# Safety_Valve.net
KiCad netlist of a schematic drawn in EAGLE
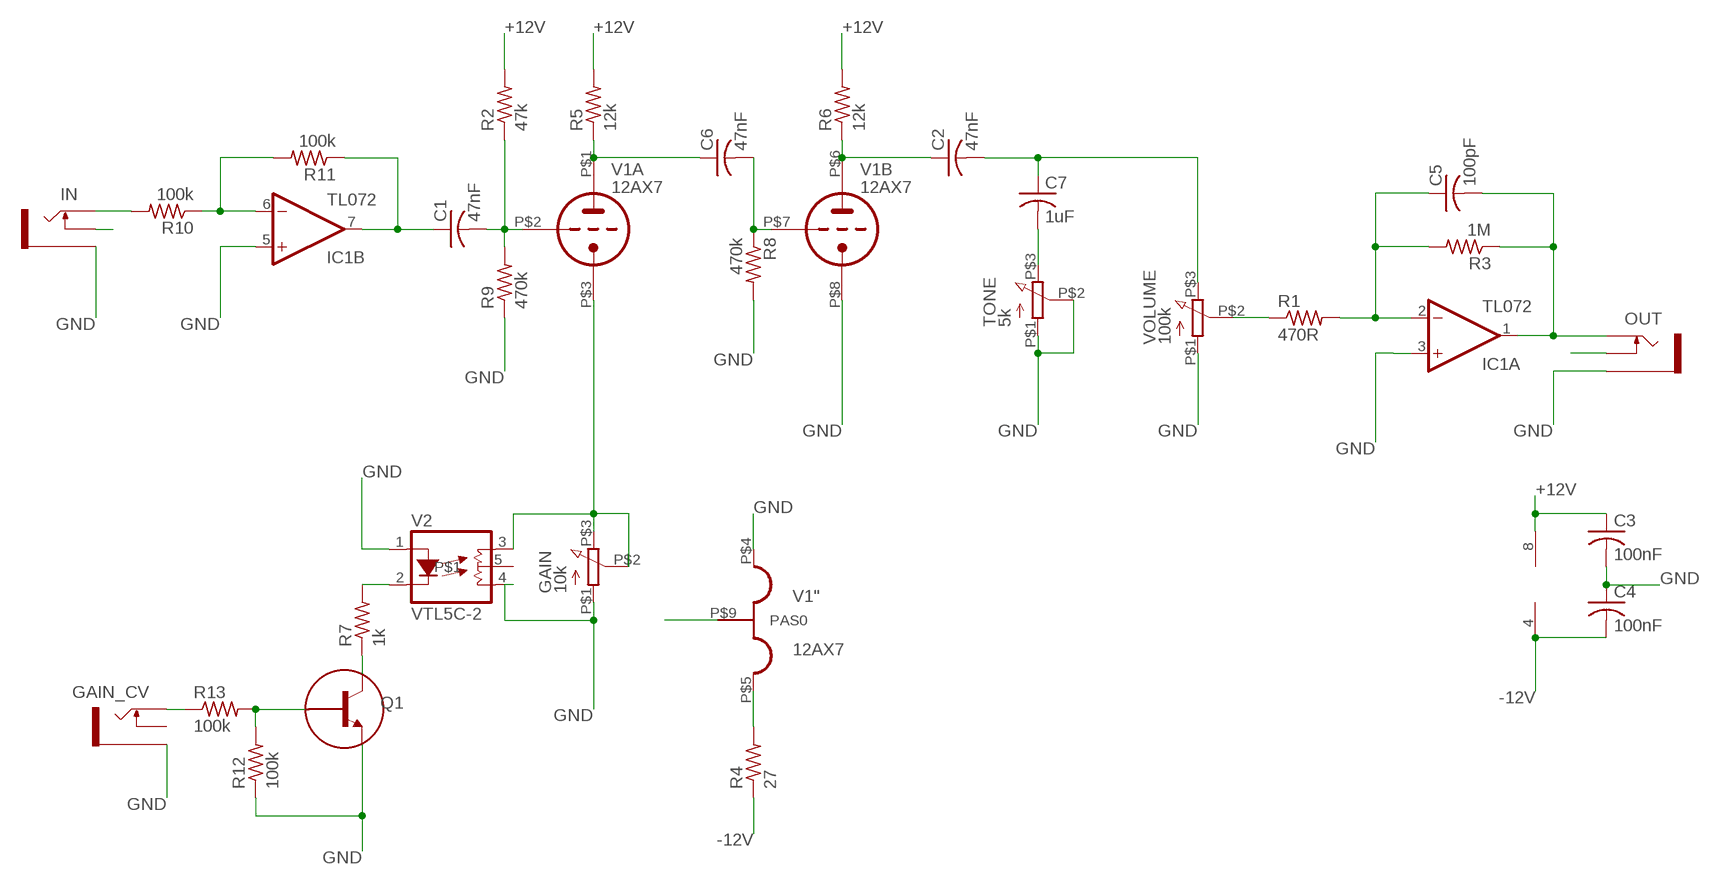
[diagram p0: schematic, sheet 1]
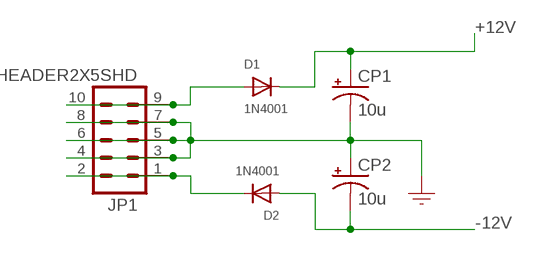
[diagram p1: schematic, sheet 2]

(export (version "E")
  (design (tool "Eeschema 10.0.6"))
  (components
    (comp (ref "CP1")
      (value "10u")
      (footprint "eagle-import:SANYO-OSCON_D")
      (fields (field (name "SPICEPREFIX") "C"))
      (libsource (lib "eagle-import") (part "CAPACITOR_POL-USSANYO_D"))
    )
    (comp (ref "CP2")
      (value "10u")
      (footprint "eagle-import:SANYO-OSCON_D")
      (fields (field (name "SPICEPREFIX") "C"))
      (libsource (lib "eagle-import") (part "CAPACITOR_POL-USSANYO_D"))
    )
    (comp (ref "D1")
      (value "1N4001")
      (footprint "eagle-import:DO-41")
      (fields (field (name "SPICEMODEL") "DMOD") (field (name "SPICEPREFIX") "D"))
      (libsource (lib "eagle-import") (part "DIODEDO-41"))
    )
    (comp (ref "D2")
      (value "1N4001")
      (footprint "eagle-import:DO-41")
      (fields (field (name "SPICEMODEL") "DMOD") (field (name "SPICEPREFIX") "D"))
      (libsource (lib "eagle-import") (part "DIODEDO-41"))
    )
    (comp (ref "JP1")
      (value "HEADER2X5SHD")
      (footprint "eagle-import:2X5-SHROUDED")
      (fields (field (name "SPICEMODEL") "EuroPower") (field (name "SPICEPREFIX") "X"))
      (libsource (lib "eagle-import") (part "HEADER2X5SHD"))
    )
    (comp (ref "C1")
      (value "47nF")
      (footprint "eagle-import:C025-024X044")
      (fields (field (name "SPICEPREFIX") "C"))
      (libsource (lib "eagle-import") (part "CAPACITOR-US025-024X044"))
    )
    (comp (ref "C2")
      (value "47nF")
      (footprint "eagle-import:C025-024X044")
      (fields (field (name "SPICEPREFIX") "C"))
      (libsource (lib "eagle-import") (part "CAPACITOR-US025-024X044"))
    )
    (comp (ref "C3")
      (value "100nF")
      (footprint "eagle-import:C025-024X044")
      (fields (field (name "SPICEPREFIX") "C"))
      (libsource (lib "eagle-import") (part "CAPACITOR-US025-024X044"))
    )
    (comp (ref "C4")
      (value "100nF")
      (footprint "eagle-import:C025-024X044")
      (fields (field (name "SPICEPREFIX") "C"))
      (libsource (lib "eagle-import") (part "CAPACITOR-US025-024X044"))
    )
    (comp (ref "C5")
      (value "100pF")
      (footprint "eagle-import:C025-024X044")
      (fields (field (name "SPICEPREFIX") "C"))
      (libsource (lib "eagle-import") (part "CAPACITOR-US025-024X044"))
    )
    (comp (ref "C6")
      (value "47nF")
      (footprint "eagle-import:C025-024X044")
      (fields (field (name "SPICEPREFIX") "C"))
      (libsource (lib "eagle-import") (part "CAPACITOR-US025-024X044"))
    )
    (comp (ref "C7")
      (value "1uF")
      (footprint "eagle-import:C050-024X044")
      (fields (field (name "SPICEPREFIX") "C"))
      (libsource (lib "eagle-import") (part "CAPACITOR-US050-024X044"))
    )
    (comp (ref "GAIN")
      (value "10k")
      (footprint "eagle-import:POTENTIOMETER_9MM")
      (fields (field (name "SPICEPREFIX") "X"))
      (libsource (lib "eagle-import") (part "RESISTOR_VARIABLE9MM_POT"))
    )
    (comp (ref "GAIN_CV")
      (value "SOCKET_MONO_3.5MMPJ301M-12")
      (footprint "eagle-import:PJ301M-12")
      (fields (field (name "SPICEMODEL") "SocketMonoSigIn") (field (name "SPICEPREFIX") "X"))
      (libsource (lib "eagle-import") (part "SOCKET_MONO_3.5MMPJ301M-12"))
    )
    (comp (ref "IC1")
      (value "TL072")
      (footprint "eagle-import:DIL08")
      (fields (field (name "SPICEMODEL") "TL072") (field (name "SPICEPREFIX") "X"))
      (libsource (lib "eagle-import") (part "OPAMP_DUALP"))
    )
    (comp (ref "IN")
      (value "SOCKET_MONO_3.5MMPJ301M-12")
      (footprint "eagle-import:PJ301M-12")
      (fields (field (name "SPICEMODEL") "SocketMonoSigIn") (field (name "SPICEPREFIX") "X"))
      (libsource (lib "eagle-import") (part "SOCKET_MONO_3.5MMPJ301M-12"))
    )
    (comp (ref "OUT")
      (value "SOCKET_MONO_3.5MMPJ301M-12")
      (footprint "eagle-import:PJ301M-12")
      (fields (field (name "SPICEMODEL") "SocketMono") (field (name "SPICEPREFIX") "X"))
      (libsource (lib "eagle-import") (part "SOCKET_MONO_3.5MMPJ301M-12"))
    )
    (comp (ref "Q1")
      (value "TRANSISTOR_NPNSOT23")
      (footprint "eagle-import:SOT23")
      (libsource (lib "eagle-import") (part "TRANSISTOR_NPNSOT23"))
    )
    (comp (ref "R1")
      (value "470R")
      (footprint "eagle-import:0207_10")
      (fields (field (name "SPICEPREFIX") "R"))
      (libsource (lib "eagle-import") (part "RESISTOR_US0207/10"))
    )
    (comp (ref "R2")
      (value "47k")
      (footprint "eagle-import:0207_10")
      (fields (field (name "SPICEPREFIX") "R"))
      (libsource (lib "eagle-import") (part "RESISTOR_US0207/10"))
    )
    (comp (ref "R3")
      (value "1M")
      (footprint "eagle-import:0207_10")
      (fields (field (name "SPICEPREFIX") "R"))
      (libsource (lib "eagle-import") (part "RESISTOR_US0207/10"))
    )
    (comp (ref "R4")
      (value "27")
      (footprint "eagle-import:0207_10")
      (fields (field (name "SPICEPREFIX") "R"))
      (libsource (lib "eagle-import") (part "RESISTOR_US0207/10"))
    )
    (comp (ref "R5")
      (value "12k")
      (footprint "eagle-import:0207_10")
      (fields (field (name "SPICEPREFIX") "R"))
      (libsource (lib "eagle-import") (part "RESISTOR_US0207/10"))
    )
    (comp (ref "R6")
      (value "12k")
      (footprint "eagle-import:0207_10")
      (fields (field (name "SPICEPREFIX") "R"))
      (libsource (lib "eagle-import") (part "RESISTOR_US0207/10"))
    )
    (comp (ref "R7")
      (value "1k")
      (footprint "eagle-import:0207_10")
      (fields (field (name "SPICEPREFIX") "R"))
      (libsource (lib "eagle-import") (part "RESISTOR_US0207/10"))
    )
    (comp (ref "R8")
      (value "470k")
      (footprint "eagle-import:0207_10")
      (fields (field (name "SPICEPREFIX") "R"))
      (libsource (lib "eagle-import") (part "RESISTOR_US0207/10"))
    )
    (comp (ref "R9")
      (value "470k")
      (footprint "eagle-import:0207_10")
      (fields (field (name "SPICEPREFIX") "R"))
      (libsource (lib "eagle-import") (part "RESISTOR_US0207/10"))
    )
    (comp (ref "R10")
      (value "100k")
      (footprint "eagle-import:0207_10")
      (fields (field (name "SPICEPREFIX") "R"))
      (libsource (lib "eagle-import") (part "RESISTOR_US0207/10"))
    )
    (comp (ref "R11")
      (value "100k")
      (footprint "eagle-import:0207_10")
      (fields (field (name "SPICEPREFIX") "R"))
      (libsource (lib "eagle-import") (part "RESISTOR_US0207/10"))
    )
    (comp (ref "R12")
      (value "100k")
      (footprint "eagle-import:0207_10")
      (fields (field (name "SPICEPREFIX") "R"))
      (libsource (lib "eagle-import") (part "RESISTOR_US0207/10"))
    )
    (comp (ref "R13")
      (value "100k")
      (footprint "eagle-import:0207_10")
      (fields (field (name "SPICEPREFIX") "R"))
      (libsource (lib "eagle-import") (part "RESISTOR_US0207/10"))
    )
    (comp (ref "TONE")
      (value "5k")
      (footprint "eagle-import:POTENTIOMETER_9MM")
      (fields (field (name "SPICEPREFIX") "X"))
      (libsource (lib "eagle-import") (part "RESISTOR_VARIABLE9MM_POT"))
    )
    (comp (ref "V1")
      (value "12AX7")
      (footprint "eagle-import:12AX7")
      (fields (field (name "SPICEMODEL") "12ax7") (field (name "SPICEPREFIX") "X"))
      (libsource (lib "eagle-import") (part "VALVE_12AX7-P"))
    )
    (comp (ref "V2")
      (value "VTL5C-2")
      (footprint "eagle-import:VTL5C-2")
      (libsource (lib "eagle-import") (part "VTL5C-2"))
    )
    (comp (ref "VOLUME")
      (value "100k")
      (footprint "eagle-import:POTENTIOMETER_9MM")
      (fields (field (name "SPICEPREFIX") "X"))
      (libsource (lib "eagle-import") (part "RESISTOR_VARIABLE9MM_POT"))
    )
  )
  (nets
    (net (code "1") (name "+12V") (class "Default")
      (node (ref "C3") (pin "1") (pinfunction "1_1") (pintype "passive"))
      (node (ref "CP1") (pin "+") (pinfunction "+_+") (pintype "passive"))
      (node (ref "D1") (pin "C") (pinfunction "C_C") (pintype "passive"))
      (node (ref "IC1") (pin "8") (pinfunction "V+_8") (pintype "power_in"))
      (node (ref "R2") (pin "2") (pinfunction "2_2") (pintype "passive"))
      (node (ref "R5") (pin "2") (pinfunction "2_2") (pintype "passive"))
      (node (ref "R6") (pin "2") (pinfunction "2_2") (pintype "passive"))
    )
    (net (code "2") (name "-12V") (class "Default")
      (node (ref "C4") (pin "2") (pinfunction "2_2") (pintype "passive"))
      (node (ref "CP2") (pin "-") (pinfunction "-_-") (pintype "passive"))
      (node (ref "D2") (pin "A") (pinfunction "A_A") (pintype "passive"))
      (node (ref "IC1") (pin "4") (pinfunction "V-_4") (pintype "power_in"))
      (node (ref "R4") (pin "1") (pinfunction "1_1") (pintype "passive"))
    )
    (net (code "3") (name "GND") (class "Default")
      (node (ref "C3") (pin "2") (pinfunction "2_2") (pintype "passive"))
      (node (ref "C4") (pin "1") (pinfunction "1_1") (pintype "passive"))
      (node (ref "CP1") (pin "-") (pinfunction "-_-") (pintype "passive"))
      (node (ref "CP2") (pin "+") (pinfunction "+_+") (pintype "passive"))
      (node (ref "GAIN") (pin "P$1") (pinfunction "1_P$1") (pintype "passive"))
      (node (ref "GAIN_CV") (pin "GND") (pinfunction "SLEEVE_GND") (pintype "passive"))
      (node (ref "IC1") (pin "3") (pinfunction "+IN_3") (pintype "input"))
      (node (ref "IC1") (pin "5") (pinfunction "+IN_5") (pintype "input"))
      (node (ref "IN") (pin "GND") (pinfunction "SLEEVE_GND") (pintype "passive"))
      (node (ref "JP1") (pin "3") (pinfunction "3_3") (pintype "passive"))
      (node (ref "JP1") (pin "4") (pinfunction "4_4") (pintype "passive"))
      (node (ref "JP1") (pin "5") (pinfunction "5_5") (pintype "passive"))
      (node (ref "JP1") (pin "6") (pinfunction "6_6") (pintype "passive"))
      (node (ref "JP1") (pin "7") (pinfunction "7_7") (pintype "passive"))
      (node (ref "JP1") (pin "8") (pinfunction "8_8") (pintype "passive"))
      (node (ref "OUT") (pin "GND") (pinfunction "SLEEVE_GND") (pintype "passive"))
      (node (ref "Q1") (pin "2") (pinfunction "E_2") (pintype "passive"))
      (node (ref "R12") (pin "1") (pinfunction "1_1") (pintype "passive"))
      (node (ref "R8") (pin "2") (pinfunction "2_2") (pintype "passive"))
      (node (ref "R9") (pin "1") (pinfunction "1_1") (pintype "passive"))
      (node (ref "TONE") (pin "P$1") (pinfunction "1_P$1") (pintype "passive"))
      (node (ref "TONE") (pin "P$2") (pinfunction "2_P$2") (pintype "passive"))
      (node (ref "V1") (pin "P$4") (pinfunction "H1_P$4") (pintype "passive"))
      (node (ref "V1") (pin "P$8") (pinfunction "TK_P$8") (pintype "passive"))
      (node (ref "V2") (pin "1") (pinfunction "A_1") (pintype "passive"))
      (node (ref "V2") (pin "4") (pinfunction "L2_4") (pintype "passive"))
      (node (ref "VOLUME") (pin "P$1") (pinfunction "1_P$1") (pintype "passive"))
    )
    (net (code "4") (name "Net-(D1-PadA)") (class "Default")
      (node (ref "D1") (pin "A") (pinfunction "A_A") (pintype "passive"))
      (node (ref "JP1") (pin "10") (pinfunction "10_10") (pintype "passive"))
      (node (ref "JP1") (pin "9") (pinfunction "9_9") (pintype "passive"))
    )
    (net (code "5") (name "Net-(D2-PadC)") (class "Default")
      (node (ref "D2") (pin "C") (pinfunction "C_C") (pintype "passive"))
      (node (ref "JP1") (pin "1") (pinfunction "1_1") (pintype "passive"))
      (node (ref "JP1") (pin "2") (pinfunction "2_2") (pintype "passive"))
    )
    (net (code "6") (name "Net-(GAIN-2)") (class "Default")
      (node (ref "GAIN") (pin "P$2") (pinfunction "2_P$2") (pintype "passive"))
      (node (ref "GAIN") (pin "P$3") (pinfunction "3_P$3") (pintype "passive"))
      (node (ref "V1") (pin "P$3") (pinfunction "TK_P$3") (pintype "passive"))
      (node (ref "V2") (pin "3") (pinfunction "L1_3") (pintype "passive"))
    )
    (net (code "7") (name "Net-(GAIN_CV-PadTIP)") (class "Default")
      (node (ref "GAIN_CV") (pin "TIP") (pinfunction "TIP_TIP") (pintype "passive"))
      (node (ref "R13") (pin "1") (pinfunction "1_1") (pintype "passive"))
    )
    (net (code "8") (name "Net-(IC1A--IN)") (class "Default")
      (node (ref "C5") (pin "1") (pinfunction "1_1") (pintype "passive"))
      (node (ref "IC1") (pin "2") (pinfunction "-IN_2") (pintype "input"))
      (node (ref "R1") (pin "2") (pinfunction "2_2") (pintype "passive"))
      (node (ref "R3") (pin "2") (pinfunction "2_2") (pintype "passive"))
    )
    (net (code "9") (name "Net-(IC1A-OUT)") (class "Default")
      (node (ref "C5") (pin "2") (pinfunction "2_2") (pintype "passive"))
      (node (ref "IC1") (pin "1") (pinfunction "OUT_1") (pintype "output"))
      (node (ref "OUT") (pin "TIP") (pinfunction "TIP_TIP") (pintype "passive"))
      (node (ref "R3") (pin "1") (pinfunction "1_1") (pintype "passive"))
    )
    (net (code "10") (name "Net-(IC1B--IN)") (class "Default")
      (node (ref "IC1") (pin "6") (pinfunction "-IN_6") (pintype "input"))
      (node (ref "R10") (pin "1") (pinfunction "1_1") (pintype "passive"))
      (node (ref "R11") (pin "2") (pinfunction "2_2") (pintype "passive"))
    )
    (net (code "11") (name "Net-(IC1B-OUT)") (class "Default")
      (node (ref "C1") (pin "1") (pinfunction "1_1") (pintype "passive"))
      (node (ref "IC1") (pin "7") (pinfunction "OUT_7") (pintype "output"))
      (node (ref "R11") (pin "1") (pinfunction "1_1") (pintype "passive"))
    )
    (net (code "12") (name "Net-(IN-PadTIP)") (class "Default")
      (node (ref "IN") (pin "TIP") (pinfunction "TIP_TIP") (pintype "passive"))
      (node (ref "R10") (pin "2") (pinfunction "2_2") (pintype "passive"))
    )
    (net (code "13") (name "Net-(Q1-B)") (class "Default")
      (node (ref "Q1") (pin "1") (pinfunction "B_1") (pintype "passive"))
      (node (ref "R12") (pin "2") (pinfunction "2_2") (pintype "passive"))
      (node (ref "R13") (pin "2") (pinfunction "2_2") (pintype "passive"))
    )
    (net (code "14") (name "Net-(Q1-C)") (class "Default")
      (node (ref "Q1") (pin "3") (pinfunction "C_3") (pintype "passive"))
      (node (ref "R7") (pin "1") (pinfunction "1_1") (pintype "passive"))
    )
    (net (code "15") (name "Net-(TONE-3)") (class "Default")
      (node (ref "C7") (pin "2") (pinfunction "2_2") (pintype "passive"))
      (node (ref "TONE") (pin "P$3") (pinfunction "3_P$3") (pintype "passive"))
    )
    (net (code "16") (name "Net-(V1A-H3)") (class "Default")
      (node (ref "R4") (pin "2") (pinfunction "2_2") (pintype "passive"))
      (node (ref "V1") (pin "P$5") (pinfunction "H3_P$5") (pintype "passive"))
    )
    (net (code "17") (name "Net-(V1B-TA)") (class "Default")
      (node (ref "C6") (pin "1") (pinfunction "1_1") (pintype "passive"))
      (node (ref "R5") (pin "1") (pinfunction "1_1") (pintype "passive"))
      (node (ref "V1") (pin "P$1") (pinfunction "TA_P$1") (pintype "passive"))
    )
    (net (code "18") (name "Net-(V1B-TG)") (class "Default")
      (node (ref "C1") (pin "2") (pinfunction "2_2") (pintype "passive"))
      (node (ref "R2") (pin "1") (pinfunction "1_1") (pintype "passive"))
      (node (ref "R9") (pin "2") (pinfunction "2_2") (pintype "passive"))
      (node (ref "V1") (pin "P$2") (pinfunction "TG_P$2") (pintype "passive"))
    )
    (net (code "19") (name "Net-(V1C-TA)") (class "Default")
      (node (ref "C2") (pin "1") (pinfunction "1_1") (pintype "passive"))
      (node (ref "R6") (pin "1") (pinfunction "1_1") (pintype "passive"))
      (node (ref "V1") (pin "P$6") (pinfunction "TA_P$6") (pintype "passive"))
    )
    (net (code "20") (name "Net-(V1C-TG)") (class "Default")
      (node (ref "C6") (pin "2") (pinfunction "2_2") (pintype "passive"))
      (node (ref "R8") (pin "1") (pinfunction "1_1") (pintype "passive"))
      (node (ref "V1") (pin "P$7") (pinfunction "TG_P$7") (pintype "passive"))
    )
    (net (code "21") (name "Net-(V2-C)") (class "Default")
      (node (ref "R7") (pin "2") (pinfunction "2_2") (pintype "passive"))
      (node (ref "V2") (pin "2") (pinfunction "C_2") (pintype "passive"))
    )
    (net (code "22") (name "Net-(VOLUME-2)") (class "Default")
      (node (ref "R1") (pin "1") (pinfunction "1_1") (pintype "passive"))
      (node (ref "VOLUME") (pin "P$2") (pinfunction "2_P$2") (pintype "passive"))
    )
    (net (code "23") (name "Net-(VOLUME-3)") (class "Default")
      (node (ref "C2") (pin "2") (pinfunction "2_2") (pintype "passive"))
      (node (ref "C7") (pin "1") (pinfunction "1_1") (pintype "passive"))
      (node (ref "VOLUME") (pin "P$3") (pinfunction "3_P$3") (pintype "passive"))
    )
    (net (code "24") (name "unconnected-(GAIN_CV-SWITCH-PadNORM)") (class "Default")
      (node (ref "GAIN_CV") (pin "NORM") (pinfunction "SWITCH_NORM") (pintype "passive"))
    )
    (net (code "25") (name "unconnected-(IN-SWITCH-PadNORM)") (class "Default")
      (node (ref "IN") (pin "NORM") (pinfunction "SWITCH_NORM") (pintype "passive"))
    )
    (net (code "26") (name "unconnected-(OUT-SWITCH-PadNORM)") (class "Default")
      (node (ref "OUT") (pin "NORM") (pinfunction "SWITCH_NORM") (pintype "passive"))
    )
    (net (code "27") (name "unconnected-(V1A-PAS0-PadP$9)") (class "Default")
      (node (ref "V1") (pin "P$9") (pinfunction "PAS0_P$9") (pintype "bidirectional"))
    )
    (net (code "28") (name "unconnected-(V2-P$1-Pad5)") (class "Default")
      (node (ref "V2") (pin "5") (pinfunction "P$1_5") (pintype "passive"))
    )
  )
)
